# Buzzer.net
KiCad netlist of a schematic drawn in Altium Designer
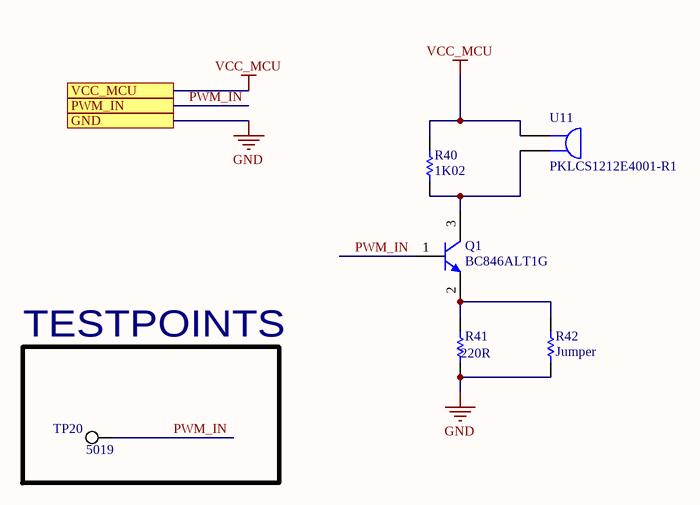
[diagram p0: Buzzer.SchDoc]

(export (version "E")
  (design (tool "Eeschema 10.0.6"))
  (components
    (comp (ref "Q1")
      (value "BC846ALT1G")
      (footprint "ONSC-SOT-23-3-318-08_V")
      (description "General Purpose Transistor, NPN Silicon, 3-Pin SOT-23, Pb-Free, Tape and Reel")
      (fields (field (name "MANUFACTURER") "On Semiconductor"))
      (libsource (lib "Altium Content Vault") (part "ONSC-NPN-B1E2C3-3"))
    )
    (comp (ref "R40")
      (value "1K02")
      (footprint "RESC0603(1608)_N")
      (description "1K02 0.1W 1% 0603 (1608 Metric)  SMD")
      (fields (field (name "POWER") "0.1 W") (field (name "TOLERANCE") "1 %"))
      (libsource (lib "Altium Content Vault") (part "RES"))
    )
    (comp (ref "R41")
      (value "220R")
      (footprint "RESC0805(2012)_L")
      (description "220R 0.125W 5% 0805 (2012 Metric)  SMD")
      (fields (field (name "POWER") "0.125 W") (field (name "TOLERANCE") "5 %"))
      (libsource (lib "Altium Content Vault") (part "RES"))
    )
    (comp (ref "R42")
      (value "Jumper")
      (footprint "RESC0603(1608)_N")
      (description "Jumper 0603 (1608 Metric)")
      (fields (field (name "POWER") "None"))
      (libsource (lib "Altium Content Vault") (part "RES"))
    )
    (comp (ref "TP20")
      (value "5019")
      (footprint "KSTN-5019_V")
      (description "Test Point, 1 Position SMD, RoHS, Tape and Reel")
      (libsource (lib "Altium Content Vault") (part "TESTPOINT_WHITE"))
    )
    (comp (ref "U11")
      (value "PKLCS1212E4001-R1")
      (footprint "MURA-PKLCS1212E4001-R1-2_V")
      (description "Piezoelectric Sound Component, 4 KHz, -20 to 70 degC, 2-Pin SMD, RoHS, Tape and Reel")
      (fields (field (name "MANUFACTURER") "Murata"))
      (libsource (lib "Altium Content Vault") (part "MURA-PKLCS1212E4001-R1-2"))
    )
  )
  (nets
    (net (code "1") (name "/PWM_IN") (class "Default")
      (node (ref "Q1") (pin "1") (pinfunction "B_1") (pintype "passive"))
      (node (ref "TP20") (pin "1") (pinfunction "1_1") (pintype "passive"))
    )
    (net (code "2") (name "GND") (class "Default")
      (node (ref "R41") (pin "1") (pinfunction "1_1") (pintype "passive"))
      (node (ref "R42") (pin "1") (pinfunction "1_1") (pintype "passive"))
    )
    (net (code "3") (name "Net-(Q1-C)") (class "Default")
      (node (ref "Q1") (pin "3") (pinfunction "C_3") (pintype "passive"))
      (node (ref "R40") (pin "1") (pinfunction "1_1") (pintype "passive"))
      (node (ref "U11") (pin "2") (pinfunction "2_2") (pintype "passive"))
    )
    (net (code "4") (name "Net-(Q1-E)") (class "Default")
      (node (ref "Q1") (pin "2") (pinfunction "E_2") (pintype "passive"))
      (node (ref "R41") (pin "2") (pinfunction "2_2") (pintype "passive"))
      (node (ref "R42") (pin "2") (pinfunction "2_2") (pintype "passive"))
    )
    (net (code "5") (name "VCC_MCU") (class "Default")
      (node (ref "R40") (pin "2") (pinfunction "2_2") (pintype "passive"))
      (node (ref "U11") (pin "1") (pinfunction "1_1") (pintype "passive"))
    )
  )
)
